# SCX10.net
KiCad netlist of a schematic drawn in Altium Designer
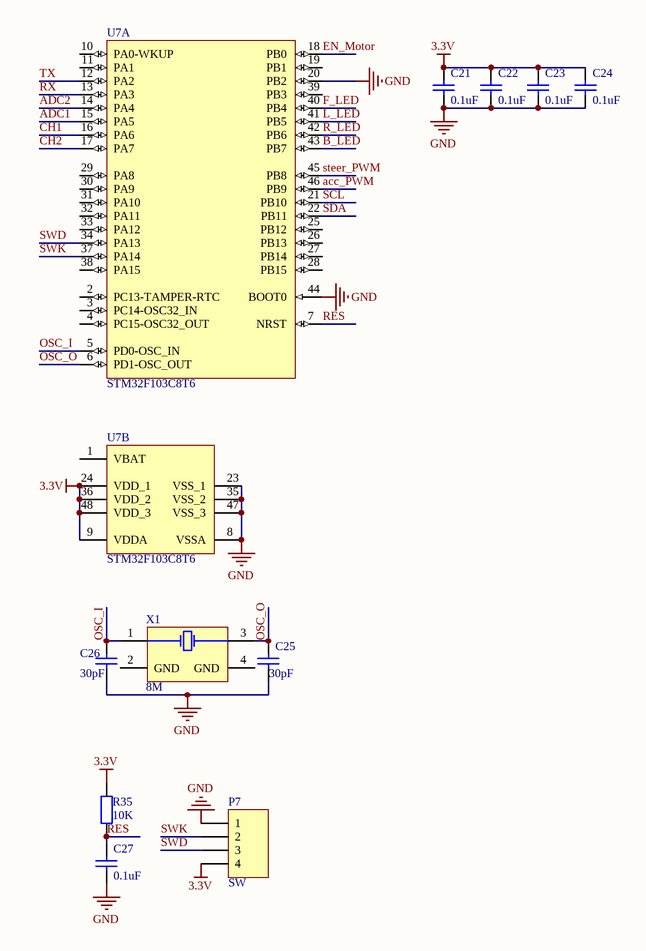
[diagram p0: SCX10.SchDoc]

(export (version "E")
  (design (tool "Eeschema 10.0.6"))
  (components
    (comp (ref "C21")
      (value "0.1uF")
      (footprint "C0603")
      (description "Capacitor")
      (fields (field (name "PUBLISHER") "Altium Limited"))
      (libsource (lib "Miscellaneous Devices") (part "Cap"))
    )
    (comp (ref "C22")
      (value "0.1uF")
      (footprint "C0603")
      (description "Capacitor")
      (fields (field (name "PUBLISHER") "Altium Limited"))
      (libsource (lib "Miscellaneous Devices") (part "Cap"))
    )
    (comp (ref "C23")
      (value "0.1uF")
      (footprint "C0603")
      (description "Capacitor")
      (fields (field (name "PUBLISHER") "Altium Limited"))
      (libsource (lib "Miscellaneous Devices") (part "Cap"))
    )
    (comp (ref "C24")
      (value "0.1uF")
      (footprint "C0603")
      (description "Capacitor")
      (fields (field (name "PUBLISHER") "Altium Limited"))
      (libsource (lib "Miscellaneous Devices") (part "Cap"))
    )
    (comp (ref "C25")
      (value "30pF")
      (footprint "C0603")
      (description "Capacitor")
      (fields (field (name "PUBLISHER") "Altium Limited"))
      (libsource (lib "Miscellaneous Devices") (part "Cap"))
    )
    (comp (ref "C26")
      (value "30pF")
      (footprint "C0603")
      (description "Capacitor")
      (fields (field (name "PUBLISHER") "Altium Limited"))
      (libsource (lib "Miscellaneous Devices") (part "Cap"))
    )
    (comp (ref "C27")
      (value "0.1uF")
      (footprint "C0603")
      (description "Capacitor")
      (fields (field (name "PUBLISHER") "Altium Limited"))
      (libsource (lib "Miscellaneous Devices") (part "Cap"))
    )
    (comp (ref "P7")
      (value "SW")
      (footprint "HDR1X4")
      (description "Header, 4-Pin")
      (fields (field (name "PUBLISHER") "Altium Limited"))
      (libsource (lib "Miscellaneous Connectors") (part "Header 4"))
    )
    (comp (ref "R35")
      (value "10K")
      (footprint "R0603")
      (description "Resistor")
      (fields (field (name "PUBLISHER") "Altium Limited"))
      (libsource (lib "Miscellaneous Devices") (part "Res2"))
    )
    (comp (ref "U7")
      (value "STM32F103C8T6")
      (footprint "STM-LQFP48-L")
      (libsource (lib "Schlib") (part "STM32F103C8T6"))
    )
    (comp (ref "X1") (value "8M") (footprint "XTAL-8M") (libsource (lib "Schlib") (part "XTAL-8M")))
  )
  (nets
    (net (code "1") (name "/ADC1") (class "Default")
      (node (ref "U7") (pin "15") (pinfunction "PA5_15") (pintype "bidirectional"))
    )
    (net (code "2") (name "/ADC2") (class "Default")
      (node (ref "U7") (pin "14") (pinfunction "PA4_14") (pintype "bidirectional"))
    )
    (net (code "3") (name "/B_LED") (class "Default")
      (node (ref "U7") (pin "43") (pinfunction "PB7_43") (pintype "bidirectional"))
    )
    (net (code "4") (name "/CH1") (class "Default")
      (node (ref "U7") (pin "16") (pinfunction "PA6_16") (pintype "bidirectional"))
    )
    (net (code "5") (name "/CH2") (class "Default")
      (node (ref "U7") (pin "17") (pinfunction "PA7_17") (pintype "bidirectional"))
    )
    (net (code "6") (name "/EN_Motor") (class "Default")
      (node (ref "U7") (pin "18") (pinfunction "PB0_18") (pintype "bidirectional"))
    )
    (net (code "7") (name "/F_LED") (class "Default")
      (node (ref "U7") (pin "40") (pinfunction "PB4_40") (pintype "bidirectional"))
    )
    (net (code "8") (name "/L_LED") (class "Default")
      (node (ref "U7") (pin "41") (pinfunction "PB5_41") (pintype "bidirectional"))
    )
    (net (code "9") (name "/OSC_I") (class "Default")
      (node (ref "C26") (pin "2") (pinfunction "2_2") (pintype "passive"))
      (node (ref "U7") (pin "5") (pinfunction "PD0-OSC_IN_5") (pintype "bidirectional"))
      (node (ref "X1") (pin "1") (pinfunction "X1_1") (pintype "passive"))
    )
    (net (code "10") (name "/OSC_O") (class "Default")
      (node (ref "C25") (pin "2") (pinfunction "2_2") (pintype "passive"))
      (node (ref "U7") (pin "6") (pinfunction "PD1-OSC_OUT_6") (pintype "bidirectional"))
      (node (ref "X1") (pin "3") (pinfunction "X2_3") (pintype "passive"))
    )
    (net (code "11") (name "/RES") (class "Default")
      (node (ref "C27") (pin "2") (pinfunction "2_2") (pintype "passive"))
      (node (ref "R35") (pin "1") (pinfunction "1_1") (pintype "passive"))
      (node (ref "U7") (pin "7") (pinfunction "NRST_7") (pintype "bidirectional"))
    )
    (net (code "12") (name "/RX") (class "Default")
      (node (ref "U7") (pin "13") (pinfunction "PA3_13") (pintype "bidirectional"))
    )
    (net (code "13") (name "/R_LED") (class "Default")
      (node (ref "U7") (pin "42") (pinfunction "PB6_42") (pintype "bidirectional"))
    )
    (net (code "14") (name "/SCL") (class "Default")
      (node (ref "U7") (pin "21") (pinfunction "PB10_21") (pintype "bidirectional"))
    )
    (net (code "15") (name "/SDA") (class "Default")
      (node (ref "U7") (pin "22") (pinfunction "PB11_22") (pintype "bidirectional"))
    )
    (net (code "16") (name "/SWD") (class "Default")
      (node (ref "P7") (pin "3") (pinfunction "3_3") (pintype "passive"))
      (node (ref "U7") (pin "34") (pinfunction "PA13_34") (pintype "bidirectional"))
    )
    (net (code "17") (name "/SWK") (class "Default")
      (node (ref "P7") (pin "2") (pinfunction "2_2") (pintype "passive"))
      (node (ref "U7") (pin "37") (pinfunction "PA14_37") (pintype "bidirectional"))
    )
    (net (code "18") (name "/TX") (class "Default")
      (node (ref "U7") (pin "12") (pinfunction "PA2_12") (pintype "bidirectional"))
    )
    (net (code "19") (name "/acc_PWM") (class "Default")
      (node (ref "U7") (pin "46") (pinfunction "PB9_46") (pintype "bidirectional"))
    )
    (net (code "20") (name "/steer_PWM") (class "Default")
      (node (ref "U7") (pin "45") (pinfunction "PB8_45") (pintype "bidirectional"))
    )
    (net (code "21") (name "3.3V") (class "Default")
      (node (ref "C21") (pin "2") (pinfunction "2_2") (pintype "passive"))
      (node (ref "C22") (pin "2") (pinfunction "2_2") (pintype "passive"))
      (node (ref "C23") (pin "2") (pinfunction "2_2") (pintype "passive"))
      (node (ref "C24") (pin "2") (pinfunction "2_2") (pintype "passive"))
      (node (ref "P7") (pin "4") (pinfunction "4_4") (pintype "passive"))
      (node (ref "R35") (pin "2") (pinfunction "2_2") (pintype "passive"))
      (node (ref "U7") (pin "24") (pinfunction "VDD_1_24") (pintype "power_in"))
      (node (ref "U7") (pin "36") (pinfunction "VDD_2_36") (pintype "power_in"))
      (node (ref "U7") (pin "48") (pinfunction "VDD_3_48") (pintype "power_in"))
      (node (ref "U7") (pin "9") (pinfunction "VDDA_9") (pintype "power_in"))
    )
    (net (code "22") (name "GND") (class "Default")
      (node (ref "C21") (pin "1") (pinfunction "1_1") (pintype "passive"))
      (node (ref "C22") (pin "1") (pinfunction "1_1") (pintype "passive"))
      (node (ref "C23") (pin "1") (pinfunction "1_1") (pintype "passive"))
      (node (ref "C24") (pin "1") (pinfunction "1_1") (pintype "passive"))
      (node (ref "C25") (pin "1") (pinfunction "1_1") (pintype "passive"))
      (node (ref "C26") (pin "1") (pinfunction "1_1") (pintype "passive"))
      (node (ref "C27") (pin "1") (pinfunction "1_1") (pintype "passive"))
      (node (ref "P7") (pin "1") (pinfunction "1_1") (pintype "passive"))
      (node (ref "U7") (pin "20") (pinfunction "PB2_20") (pintype "bidirectional"))
      (node (ref "U7") (pin "23") (pinfunction "VSS_1_23") (pintype "power_in"))
      (node (ref "U7") (pin "35") (pinfunction "VSS_2_35") (pintype "power_in"))
      (node (ref "U7") (pin "44") (pinfunction "BOOT0_44") (pintype "input"))
      (node (ref "U7") (pin "47") (pinfunction "VSS_3_47") (pintype "power_in"))
      (node (ref "U7") (pin "8") (pinfunction "VSSA_8") (pintype "power_in"))
    )
    (net (code "23") (name "unconnected-(U7A-PA0-WKUP-Pad10)") (class "Default")
      (node (ref "U7") (pin "10") (pinfunction "PA0-WKUP_10") (pintype "bidirectional"))
    )
    (net (code "24") (name "unconnected-(U7A-PA1-Pad11)") (class "Default")
      (node (ref "U7") (pin "11") (pinfunction "PA1_11") (pintype "bidirectional"))
    )
    (net (code "25") (name "unconnected-(U7A-PA8-Pad29)") (class "Default")
      (node (ref "U7") (pin "29") (pinfunction "PA8_29") (pintype "bidirectional"))
    )
    (net (code "26") (name "unconnected-(U7A-PA9-Pad30)") (class "Default")
      (node (ref "U7") (pin "30") (pinfunction "PA9_30") (pintype "bidirectional"))
    )
    (net (code "27") (name "unconnected-(U7A-PA10-Pad31)") (class "Default")
      (node (ref "U7") (pin "31") (pinfunction "PA10_31") (pintype "bidirectional"))
    )
    (net (code "28") (name "unconnected-(U7A-PA11-Pad32)") (class "Default")
      (node (ref "U7") (pin "32") (pinfunction "PA11_32") (pintype "bidirectional"))
    )
    (net (code "29") (name "unconnected-(U7A-PA12-Pad33)") (class "Default")
      (node (ref "U7") (pin "33") (pinfunction "PA12_33") (pintype "bidirectional"))
    )
    (net (code "30") (name "unconnected-(U7A-PA15-Pad38)") (class "Default")
      (node (ref "U7") (pin "38") (pinfunction "PA15_38") (pintype "bidirectional"))
    )
    (net (code "31") (name "unconnected-(U7A-PB1-Pad19)") (class "Default")
      (node (ref "U7") (pin "19") (pinfunction "PB1_19") (pintype "bidirectional"))
    )
    (net (code "32") (name "unconnected-(U7A-PB3-Pad39)") (class "Default")
      (node (ref "U7") (pin "39") (pinfunction "PB3_39") (pintype "bidirectional"))
    )
    (net (code "33") (name "unconnected-(U7A-PB12-Pad25)") (class "Default")
      (node (ref "U7") (pin "25") (pinfunction "PB12_25") (pintype "bidirectional"))
    )
    (net (code "34") (name "unconnected-(U7A-PB13-Pad26)") (class "Default")
      (node (ref "U7") (pin "26") (pinfunction "PB13_26") (pintype "bidirectional"))
    )
    (net (code "35") (name "unconnected-(U7A-PB14-Pad27)") (class "Default")
      (node (ref "U7") (pin "27") (pinfunction "PB14_27") (pintype "bidirectional"))
    )
    (net (code "36") (name "unconnected-(U7A-PB15-Pad28)") (class "Default")
      (node (ref "U7") (pin "28") (pinfunction "PB15_28") (pintype "bidirectional"))
    )
    (net (code "37") (name "unconnected-(U7A-PC13-TAMPER-RTC-Pad2)") (class "Default")
      (node (ref "U7") (pin "2") (pinfunction "PC13-TAMPER-RTC_2") (pintype "bidirectional"))
    )
    (net (code "38") (name "unconnected-(U7A-PC14-OSC32_IN-Pad3)") (class "Default")
      (node (ref "U7") (pin "3") (pinfunction "PC14-OSC32_IN_3") (pintype "bidirectional"))
    )
    (net (code "39") (name "unconnected-(U7A-PC15-OSC32_OUT-Pad4)") (class "Default")
      (node (ref "U7") (pin "4") (pinfunction "PC15-OSC32_OUT_4") (pintype "bidirectional"))
    )
    (net (code "40") (name "unconnected-(U7B-VBAT-Pad1)") (class "Default")
      (node (ref "U7") (pin "1") (pinfunction "VBAT_1") (pintype "power_in"))
    )
    (net (code "41") (name "unconnected-(X1-GND-Pad2)") (class "Default")
      (node (ref "X1") (pin "2") (pinfunction "GND_2") (pintype "power_in"))
    )
    (net (code "42") (name "unconnected-(X1-GND-Pad4)") (class "Default")
      (node (ref "X1") (pin "4") (pinfunction "GND_4") (pintype "power_in"))
    )
  )
)
